# StasDuino_V2.net
KiCad netlist of a schematic drawn in EAGLE
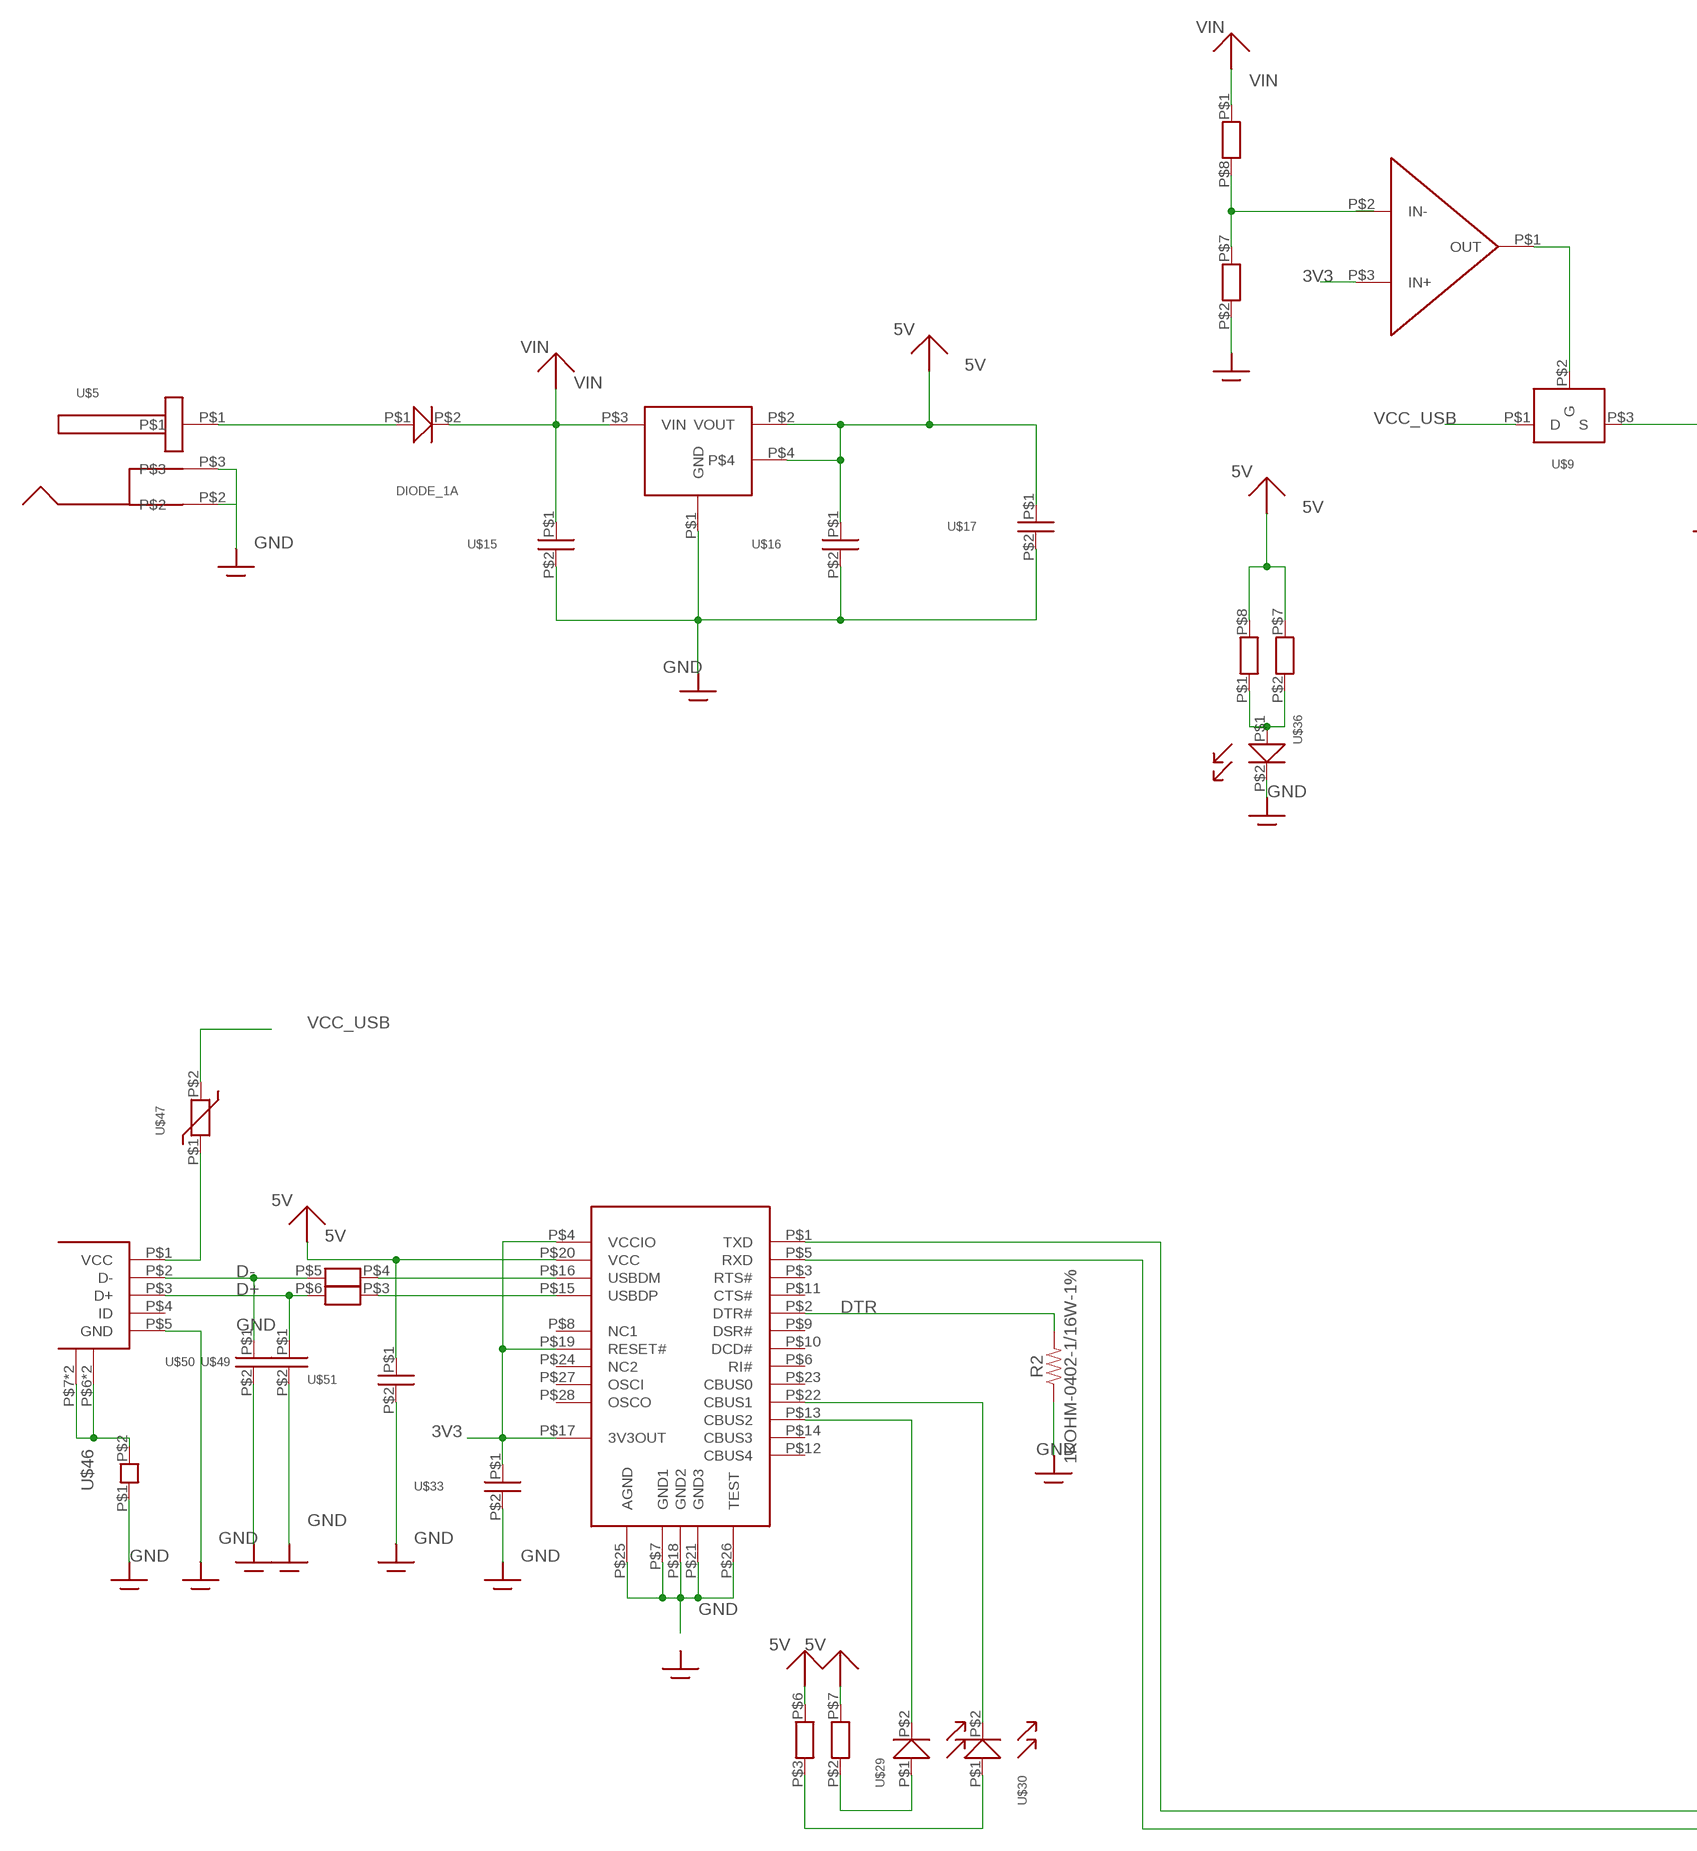
[diagram p0: schematic, sheet 1, part 1 of 2]
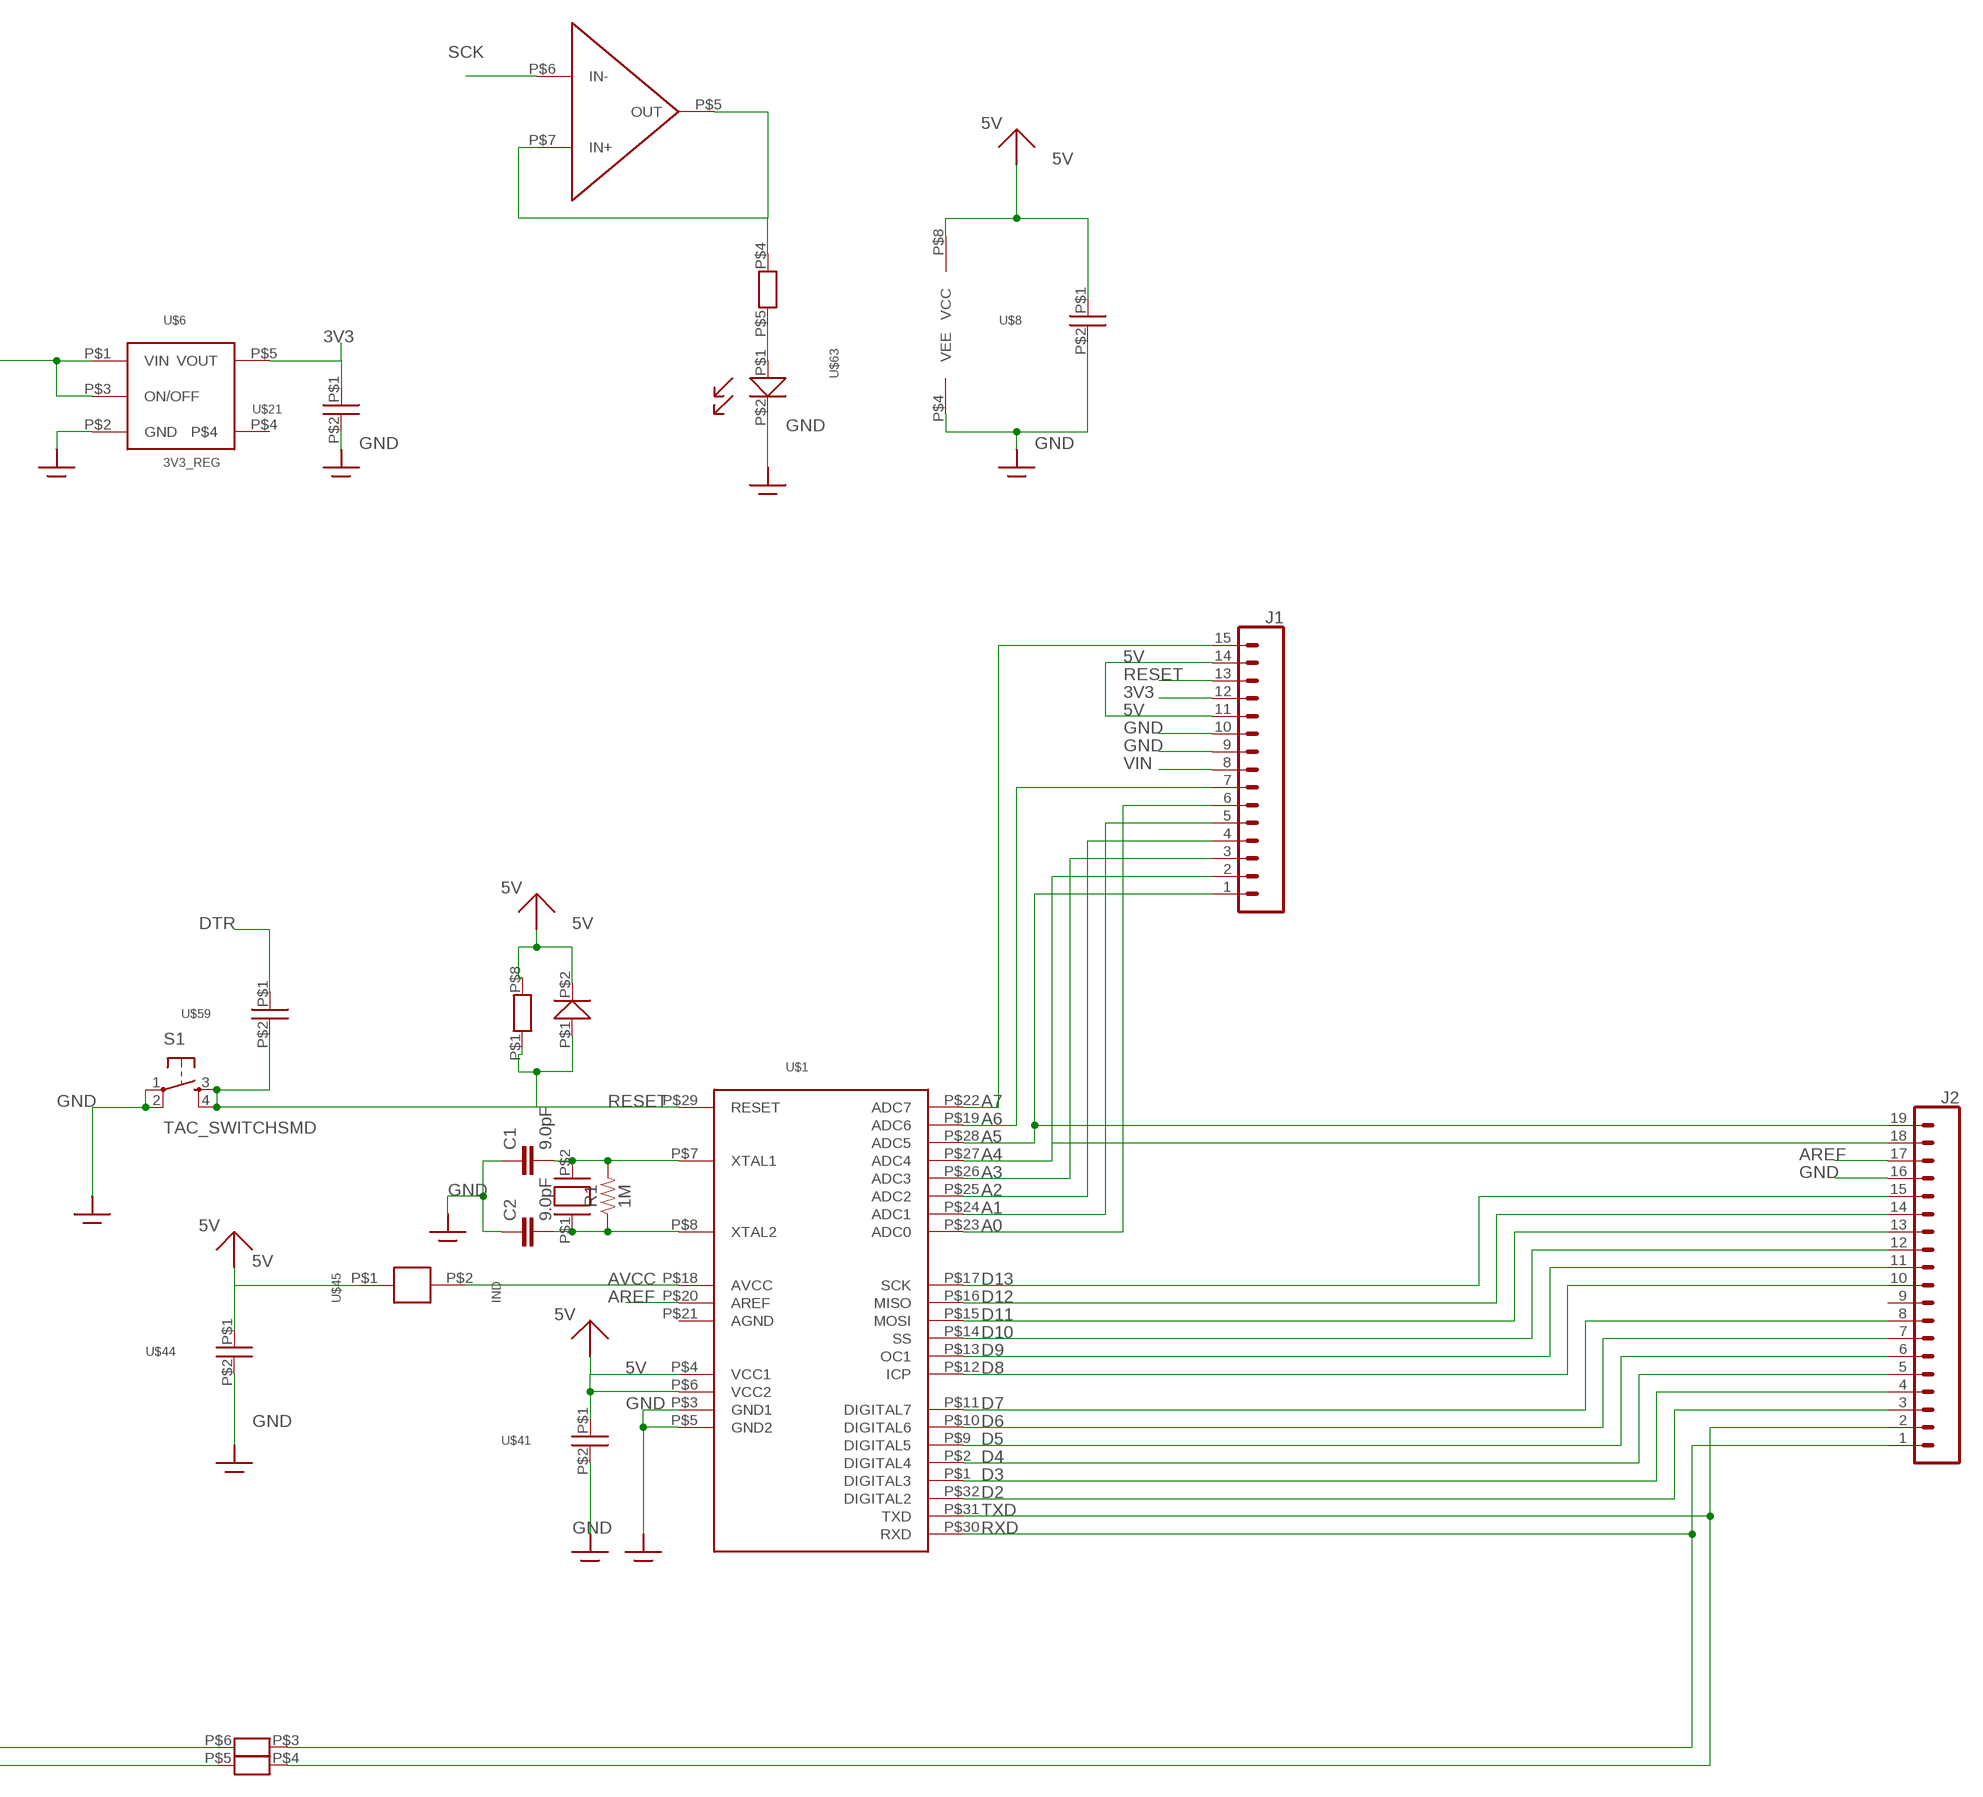
[diagram p1: schematic, sheet 1, part 2 of 2]

(export (version "E")
  (design (tool "Eeschema 10.0.6"))
  (components
    (comp (ref "C1")
      (value "9.0pF")
      (footprint "eagle-import:0603")
      (libsource (lib "eagle-import") (part "9.0PF-0603-50V-10%"))
    )
    (comp (ref "C2")
      (value "9.0pF")
      (footprint "eagle-import:0603")
      (libsource (lib "eagle-import") (part "9.0PF-0603-50V-10%"))
    )
    (comp (ref "J1")
      (value "CONN_15")
      (footprint "eagle-import:1X15")
      (libsource (lib "eagle-import") (part "CONN_15"))
    )
    (comp (ref "J2")
      (value "CONN_19")
      (footprint "eagle-import:1X19")
      (libsource (lib "eagle-import") (part "CONN_19"))
    )
    (comp (ref "R1")
      (value "1M")
      (footprint "eagle-import:0603")
      (libsource (lib "eagle-import") (part "1MOHM-0603-1/4W-5%"))
    )
    (comp (ref "R2")
      (value "1KOHM-0402-1/16W-1%")
      (footprint "eagle-import:0402")
      (libsource (lib "eagle-import") (part "1KOHM-0402-1/16W-1%"))
    )
    (comp (ref "S1")
      (value "TAC_SWITCHSMD")
      (footprint "eagle-import:TACTILE-SWITCH-SMD")
      (libsource (lib "eagle-import") (part "TAC_SWITCHSMD"))
    )
    (comp (ref "U$1")
      (value "ATMEGA328P_TQFP")
      (footprint "eagle-import:ATMEGA328P_TQFP")
      (libsource (lib "eagle-import") (part "ATMEGA328P_TQFP"))
    )
    (comp (ref "U$2")
      (value "FTDI_SERIAL")
      (footprint "eagle-import:FTDI_SERIAL")
      (libsource (lib "eagle-import") (part "FTDI_SERIAL"))
    )
    (comp (ref "U$3")
      (value "USB_MICRO")
      (footprint "eagle-import:USB_MICRO")
      (libsource (lib "eagle-import") (part "USB_MICRO"))
    )
    (comp (ref "U$4")
      (value "5V_REG")
      (footprint "eagle-import:5V_REG")
      (libsource (lib "eagle-import") (part "5V_REG"))
    )
    (comp (ref "U$5")
      (value "DC_POWERJACK")
      (footprint "eagle-import:DC_POWERJACK")
      (libsource (lib "eagle-import") (part "DC_POWERJACK"))
    )
    (comp (ref "U$6")
      (value "3V3_REG")
      (footprint "eagle-import:3V3_REG")
      (libsource (lib "eagle-import") (part "3V3_REG"))
    )
    (comp (ref "U$7")
      (value "OPAMP")
      (footprint "eagle-import:OPAMP")
      (libsource (lib "eagle-import") (part "OPAMP"))
    )
    (comp (ref "U$8")
      (value "CAP_0805")
      (footprint "eagle-import:CAP_0805")
      (libsource (lib "eagle-import") (part "CAP_0805"))
    )
    (comp (ref "U$9")
      (value "PMOS")
      (footprint "eagle-import:PMOS")
      (libsource (lib "eagle-import") (part "PMOS"))
    )
    (comp (ref "U$12")
      (value "DIODE_1A")
      (footprint "eagle-import:DIODE_1A")
      (libsource (lib "eagle-import") (part "DIODE_1A"))
    )
    (comp (ref "U$15")
      (value "CAP_0805")
      (footprint "eagle-import:CAP_0805")
      (libsource (lib "eagle-import") (part "CAP_0805"))
    )
    (comp (ref "U$16")
      (value "CAP_0805")
      (footprint "eagle-import:CAP_0805")
      (libsource (lib "eagle-import") (part "CAP_0805"))
    )
    (comp (ref "U$17")
      (value "CAP_0805")
      (footprint "eagle-import:CAP_0805")
      (libsource (lib "eagle-import") (part "CAP_0805"))
    )
    (comp (ref "U$20")
      (value "RES_ARRAY")
      (footprint "eagle-import:RES_ARRAY")
      (libsource (lib "eagle-import") (part "RES_ARRAY"))
    )
    (comp (ref "U$21")
      (value "CAP_0805")
      (footprint "eagle-import:CAP_0805")
      (libsource (lib "eagle-import") (part "CAP_0805"))
    )
    (comp (ref "U$29")
      (value "LED_0805")
      (footprint "eagle-import:LED_0805")
      (libsource (lib "eagle-import") (part "LED_0805"))
    )
    (comp (ref "U$30")
      (value "LED_0805")
      (footprint "eagle-import:LED_0805")
      (libsource (lib "eagle-import") (part "LED_0805"))
    )
    (comp (ref "U$33")
      (value "CAP_0805")
      (footprint "eagle-import:CAP_0805")
      (libsource (lib "eagle-import") (part "CAP_0805"))
    )
    (comp (ref "U$34")
      (value "RES_ARRAY")
      (footprint "eagle-import:RES_ARRAY")
      (libsource (lib "eagle-import") (part "RES_ARRAY"))
    )
    (comp (ref "U$36")
      (value "LED_0805")
      (footprint "eagle-import:LED_0805")
      (libsource (lib "eagle-import") (part "LED_0805"))
    )
    (comp (ref "U$41")
      (value "CAP_0805")
      (footprint "eagle-import:CAP_0805")
      (libsource (lib "eagle-import") (part "CAP_0805"))
    )
    (comp (ref "U$44")
      (value "CAP_0805")
      (footprint "eagle-import:CAP_0805")
      (libsource (lib "eagle-import") (part "CAP_0805"))
    )
    (comp (ref "U$45")
      (value "IND")
      (footprint "eagle-import:IND")
      (libsource (lib "eagle-import") (part "IND"))
    )
    (comp (ref "U$46")
      (value "FERRITE_BEAD")
      (footprint "eagle-import:FERRITE_BEAD")
      (libsource (lib "eagle-import") (part "FERRITE_BEAD"))
    )
    (comp (ref "U$47")
      (value "RESET_FUSE")
      (footprint "eagle-import:RESET_FUSE")
      (libsource (lib "eagle-import") (part "RESET_FUSE"))
    )
    (comp (ref "U$48")
      (value "RES_ARRAY")
      (footprint "eagle-import:RES_ARRAY")
      (libsource (lib "eagle-import") (part "RES_ARRAY"))
    )
    (comp (ref "U$49")
      (value "CAP_0805")
      (footprint "eagle-import:CAP_0805")
      (libsource (lib "eagle-import") (part "CAP_0805"))
    )
    (comp (ref "U$50")
      (value "CAP_0805")
      (footprint "eagle-import:CAP_0805")
      (libsource (lib "eagle-import") (part "CAP_0805"))
    )
    (comp (ref "U$51")
      (value "CAP_0805")
      (footprint "eagle-import:CAP_0805")
      (libsource (lib "eagle-import") (part "CAP_0805"))
    )
    (comp (ref "U$57")
      (value "CRYSTAL")
      (footprint "eagle-import:CRYSTAL")
      (libsource (lib "eagle-import") (part "CRYSTAL"))
    )
    (comp (ref "U$59")
      (value "CAP_0805")
      (footprint "eagle-import:CAP_0805")
      (libsource (lib "eagle-import") (part "CAP_0805"))
    )
    (comp (ref "U$60")
      (value "DIODE")
      (footprint "eagle-import:DIODE")
      (libsource (lib "eagle-import") (part "DIODE"))
    )
    (comp (ref "U$63")
      (value "LED_0805")
      (footprint "eagle-import:LED_0805")
      (libsource (lib "eagle-import") (part "LED_0805"))
    )
  )
  (nets
    (net (code "1") (name "/3V3") (class "Default")
      (node (ref "J1") (pin "12") (pinfunction "12_12") (pintype "passive"))
      (node (ref "U$2") (pin "P$17") (pinfunction "3V3OUT_P$17") (pintype "bidirectional"))
      (node (ref "U$2") (pin "P$19") (pinfunction "RESET#_P$19") (pintype "bidirectional"))
      (node (ref "U$2") (pin "P$4") (pinfunction "VCCIO_P$4") (pintype "bidirectional"))
      (node (ref "U$21") (pin "P$1") (pinfunction "P$1_P$1") (pintype "bidirectional"))
      (node (ref "U$33") (pin "P$1") (pinfunction "P$1_P$1") (pintype "bidirectional"))
      (node (ref "U$6") (pin "P$5") (pinfunction "VOUT_P$5") (pintype "bidirectional"))
      (node (ref "U$7") (pin "P$3") (pinfunction "IN+_P$3") (pintype "bidirectional"))
    )
    (net (code "2") (name "/5V") (class "Default")
      (node (ref "J1") (pin "11") (pinfunction "11_11") (pintype "passive"))
      (node (ref "J1") (pin "14") (pinfunction "14_14") (pintype "passive"))
      (node (ref "U$1") (pin "P$4") (pinfunction "VCC1_P$4") (pintype "bidirectional"))
      (node (ref "U$1") (pin "P$6") (pinfunction "VCC2_P$6") (pintype "bidirectional"))
      (node (ref "U$16") (pin "P$1") (pinfunction "P$1_P$1") (pintype "bidirectional"))
      (node (ref "U$17") (pin "P$1") (pinfunction "P$1_P$1") (pintype "bidirectional"))
      (node (ref "U$2") (pin "P$20") (pinfunction "VCC_P$20") (pintype "bidirectional"))
      (node (ref "U$34") (pin "P$7") (pinfunction "P$2_P$7") (pintype "bidirectional"))
      (node (ref "U$34") (pin "P$8") (pinfunction "P$2_P$8") (pintype "bidirectional"))
      (node (ref "U$4") (pin "P$2") (pinfunction "VOUT_P$2") (pintype "bidirectional"))
      (node (ref "U$4") (pin "P$4") (pinfunction "P$4_P$4") (pintype "bidirectional"))
      (node (ref "U$41") (pin "P$1") (pinfunction "P$1_P$1") (pintype "bidirectional"))
      (node (ref "U$44") (pin "P$1") (pinfunction "P$1_P$1") (pintype "bidirectional"))
      (node (ref "U$45") (pin "P$1") (pinfunction "P$1_P$1") (pintype "bidirectional"))
      (node (ref "U$48") (pin "P$6") (pinfunction "P$2_P$6") (pintype "bidirectional"))
      (node (ref "U$48") (pin "P$7") (pinfunction "P$2_P$7") (pintype "bidirectional"))
      (node (ref "U$48") (pin "P$8") (pinfunction "P$2_P$8") (pintype "bidirectional"))
      (node (ref "U$51") (pin "P$1") (pinfunction "P$1_P$1") (pintype "bidirectional"))
      (node (ref "U$60") (pin "P$2") (pinfunction "P$2_P$2") (pintype "bidirectional"))
      (node (ref "U$7") (pin "P$8") (pinfunction "VCC_P$8") (pintype "bidirectional"))
      (node (ref "U$8") (pin "P$1") (pinfunction "P$1_P$1") (pintype "bidirectional"))
    )
    (net (code "3") (name "/A0") (class "Default")
      (node (ref "J1") (pin "6") (pinfunction "6_6") (pintype "passive"))
      (node (ref "U$1") (pin "P$23") (pinfunction "ADC0_P$23") (pintype "bidirectional"))
    )
    (net (code "4") (name "/A1") (class "Default")
      (node (ref "J1") (pin "5") (pinfunction "5_5") (pintype "passive"))
      (node (ref "U$1") (pin "P$24") (pinfunction "ADC1_P$24") (pintype "bidirectional"))
    )
    (net (code "5") (name "/A2") (class "Default")
      (node (ref "J1") (pin "4") (pinfunction "4_4") (pintype "passive"))
      (node (ref "U$1") (pin "P$25") (pinfunction "ADC2_P$25") (pintype "bidirectional"))
    )
    (net (code "6") (name "/A3") (class "Default")
      (node (ref "J1") (pin "3") (pinfunction "3_3") (pintype "passive"))
      (node (ref "U$1") (pin "P$26") (pinfunction "ADC3_P$26") (pintype "bidirectional"))
    )
    (net (code "7") (name "/A4") (class "Default")
      (node (ref "J1") (pin "2") (pinfunction "2_2") (pintype "passive"))
      (node (ref "J2") (pin "18") (pinfunction "18_18") (pintype "passive"))
      (node (ref "U$1") (pin "P$27") (pinfunction "ADC4_P$27") (pintype "bidirectional"))
    )
    (net (code "8") (name "/A5") (class "Default")
      (node (ref "J1") (pin "1") (pinfunction "1_1") (pintype "passive"))
      (node (ref "J2") (pin "19") (pinfunction "19_19") (pintype "passive"))
      (node (ref "U$1") (pin "P$28") (pinfunction "ADC5_P$28") (pintype "bidirectional"))
    )
    (net (code "9") (name "/A6") (class "Default")
      (node (ref "J1") (pin "7") (pinfunction "7_7") (pintype "passive"))
      (node (ref "U$1") (pin "P$19") (pinfunction "ADC6_P$19") (pintype "bidirectional"))
    )
    (net (code "10") (name "/A7") (class "Default")
      (node (ref "J1") (pin "15") (pinfunction "15_15") (pintype "passive"))
      (node (ref "U$1") (pin "P$22") (pinfunction "ADC7_P$22") (pintype "bidirectional"))
    )
    (net (code "11") (name "/AREF") (class "Default")
      (node (ref "J2") (pin "17") (pinfunction "17_17") (pintype "passive"))
      (node (ref "U$1") (pin "P$20") (pinfunction "AREF_P$20") (pintype "bidirectional"))
    )
    (net (code "12") (name "/AVCC") (class "Default")
      (node (ref "U$1") (pin "P$18") (pinfunction "AVCC_P$18") (pintype "bidirectional"))
      (node (ref "U$45") (pin "P$2") (pinfunction "P$2_P$2") (pintype "bidirectional"))
    )
    (net (code "13") (name "/D+") (class "Default")
      (node (ref "U$20") (pin "P$6") (pinfunction "P$2_P$6") (pintype "bidirectional"))
      (node (ref "U$3") (pin "P$3") (pinfunction "D+_P$3") (pintype "bidirectional"))
      (node (ref "U$49") (pin "P$1") (pinfunction "P$1_P$1") (pintype "bidirectional"))
    )
    (net (code "14") (name "/D-") (class "Default")
      (node (ref "U$20") (pin "P$5") (pinfunction "P$2_P$5") (pintype "bidirectional"))
      (node (ref "U$3") (pin "P$2") (pinfunction "D-_P$2") (pintype "bidirectional"))
      (node (ref "U$50") (pin "P$1") (pinfunction "P$1_P$1") (pintype "bidirectional"))
    )
    (net (code "15") (name "/D2") (class "Default")
      (node (ref "J2") (pin "3") (pinfunction "3_3") (pintype "passive"))
      (node (ref "U$1") (pin "P$32") (pinfunction "DIGITAL2_P$32") (pintype "bidirectional"))
    )
    (net (code "16") (name "/D3") (class "Default")
      (node (ref "J2") (pin "4") (pinfunction "4_4") (pintype "passive"))
      (node (ref "U$1") (pin "P$1") (pinfunction "DIGITAL3_P$1") (pintype "bidirectional"))
    )
    (net (code "17") (name "/D4") (class "Default")
      (node (ref "J2") (pin "5") (pinfunction "5_5") (pintype "passive"))
      (node (ref "U$1") (pin "P$2") (pinfunction "DIGITAL4_P$2") (pintype "bidirectional"))
    )
    (net (code "18") (name "/D5") (class "Default")
      (node (ref "J2") (pin "6") (pinfunction "6_6") (pintype "passive"))
      (node (ref "U$1") (pin "P$9") (pinfunction "DIGITAL5_P$9") (pintype "bidirectional"))
    )
    (net (code "19") (name "/D6") (class "Default")
      (node (ref "J2") (pin "7") (pinfunction "7_7") (pintype "passive"))
      (node (ref "U$1") (pin "P$10") (pinfunction "DIGITAL6_P$10") (pintype "bidirectional"))
    )
    (net (code "20") (name "/D7") (class "Default")
      (node (ref "J2") (pin "8") (pinfunction "8_8") (pintype "passive"))
      (node (ref "U$1") (pin "P$11") (pinfunction "DIGITAL7_P$11") (pintype "bidirectional"))
    )
    (net (code "21") (name "/D8") (class "Default")
      (node (ref "J2") (pin "10") (pinfunction "10_10") (pintype "passive"))
      (node (ref "U$1") (pin "P$12") (pinfunction "ICP_P$12") (pintype "bidirectional"))
    )
    (net (code "22") (name "/D9") (class "Default")
      (node (ref "J2") (pin "11") (pinfunction "11_11") (pintype "passive"))
      (node (ref "U$1") (pin "P$13") (pinfunction "OC1_P$13") (pintype "bidirectional"))
    )
    (net (code "23") (name "/D10") (class "Default")
      (node (ref "J2") (pin "12") (pinfunction "12_12") (pintype "passive"))
      (node (ref "U$1") (pin "P$14") (pinfunction "SS_P$14") (pintype "bidirectional"))
    )
    (net (code "24") (name "/D11") (class "Default")
      (node (ref "J2") (pin "13") (pinfunction "13_13") (pintype "passive"))
      (node (ref "U$1") (pin "P$15") (pinfunction "MOSI_P$15") (pintype "bidirectional"))
    )
    (net (code "25") (name "/D12") (class "Default")
      (node (ref "J2") (pin "14") (pinfunction "14_14") (pintype "passive"))
      (node (ref "U$1") (pin "P$16") (pinfunction "MISO_P$16") (pintype "bidirectional"))
    )
    (net (code "26") (name "/D13") (class "Default")
      (node (ref "J2") (pin "15") (pinfunction "15_15") (pintype "passive"))
      (node (ref "U$1") (pin "P$17") (pinfunction "SCK_P$17") (pintype "bidirectional"))
    )
    (net (code "27") (name "/DTR") (class "Default")
      (node (ref "R2") (pin "2") (pinfunction "2_2") (pintype "passive"))
      (node (ref "U$2") (pin "P$2") (pinfunction "DTR#_P$2") (pintype "bidirectional"))
      (node (ref "U$59") (pin "P$1") (pinfunction "P$1_P$1") (pintype "bidirectional"))
    )
    (net (code "28") (name "/GND") (class "Default")
      (node (ref "C1") (pin "1") (pinfunction "1_1") (pintype "passive"))
      (node (ref "C2") (pin "1") (pinfunction "1_1") (pintype "passive"))
      (node (ref "J1") (pin "10") (pinfunction "10_10") (pintype "passive"))
      (node (ref "J1") (pin "9") (pinfunction "9_9") (pintype "passive"))
      (node (ref "J2") (pin "16") (pinfunction "16_16") (pintype "passive"))
      (node (ref "R2") (pin "1") (pinfunction "1_1") (pintype "passive"))
      (node (ref "S1") (pin "1") (pinfunction "1_1") (pintype "passive"))
      (node (ref "S1") (pin "2") (pinfunction "2_2") (pintype "passive"))
      (node (ref "U$1") (pin "P$3") (pinfunction "GND1_P$3") (pintype "bidirectional"))
      (node (ref "U$1") (pin "P$5") (pinfunction "GND2_P$5") (pintype "bidirectional"))
      (node (ref "U$15") (pin "P$2") (pinfunction "P$2_P$2") (pintype "bidirectional"))
      (node (ref "U$16") (pin "P$2") (pinfunction "P$2_P$2") (pintype "bidirectional"))
      (node (ref "U$17") (pin "P$2") (pinfunction "P$2_P$2") (pintype "bidirectional"))
      (node (ref "U$2") (pin "P$18") (pinfunction "GND2_P$18") (pintype "bidirectional"))
      (node (ref "U$2") (pin "P$21") (pinfunction "GND3_P$21") (pintype "bidirectional"))
      (node (ref "U$2") (pin "P$25") (pinfunction "AGND_P$25") (pintype "bidirectional"))
      (node (ref "U$2") (pin "P$26") (pinfunction "TEST_P$26") (pintype "bidirectional"))
      (node (ref "U$2") (pin "P$7") (pinfunction "GND1_P$7") (pintype "bidirectional"))
      (node (ref "U$20") (pin "P$2") (pinfunction "P$1_P$2") (pintype "bidirectional"))
      (node (ref "U$21") (pin "P$2") (pinfunction "P$2_P$2") (pintype "bidirectional"))
      (node (ref "U$3") (pin "P$5") (pinfunction "GND_P$5") (pintype "bidirectional"))
      (node (ref "U$33") (pin "P$2") (pinfunction "P$2_P$2") (pintype "bidirectional"))
      (node (ref "U$36") (pin "P$2") (pinfunction "P$2_P$2") (pintype "bidirectional"))
      (node (ref "U$4") (pin "P$1") (pinfunction "GND_P$1") (pintype "bidirectional"))
      (node (ref "U$41") (pin "P$2") (pinfunction "P$2_P$2") (pintype "bidirectional"))
      (node (ref "U$44") (pin "P$2") (pinfunction "P$2_P$2") (pintype "bidirectional"))
      (node (ref "U$46") (pin "P$1") (pinfunction "P$1_P$1") (pintype "bidirectional"))
      (node (ref "U$49") (pin "P$2") (pinfunction "P$2_P$2") (pintype "bidirectional"))
      (node (ref "U$5") (pin "P$2") (pinfunction "P$2_P$2") (pintype "bidirectional"))
      (node (ref "U$5") (pin "P$3") (pinfunction "P$3_P$3") (pintype "bidirectional"))
      (node (ref "U$50") (pin "P$2") (pinfunction "P$2_P$2") (pintype "bidirectional"))
      (node (ref "U$51") (pin "P$2") (pinfunction "P$2_P$2") (pintype "bidirectional"))
      (node (ref "U$6") (pin "P$2") (pinfunction "GND_P$2") (pintype "bidirectional"))
      (node (ref "U$63") (pin "P$2") (pinfunction "P$2_P$2") (pintype "bidirectional"))
      (node (ref "U$7") (pin "P$4") (pinfunction "VEE_P$4") (pintype "bidirectional"))
      (node (ref "U$8") (pin "P$2") (pinfunction "P$2_P$2") (pintype "bidirectional"))
    )
    (net (code "29") (name "/RESET") (class "Default")
      (node (ref "J1") (pin "13") (pinfunction "13_13") (pintype "passive"))
      (node (ref "S1") (pin "3") (pinfunction "3_3") (pintype "passive"))
      (node (ref "S1") (pin "4") (pinfunction "4_4") (pintype "passive"))
      (node (ref "U$1") (pin "P$29") (pinfunction "RESET_P$29") (pintype "bidirectional"))
      (node (ref "U$48") (pin "P$1") (pinfunction "P$1_P$1") (pintype "bidirectional"))
      (node (ref "U$59") (pin "P$2") (pinfunction "P$2_P$2") (pintype "bidirectional"))
      (node (ref "U$60") (pin "P$1") (pinfunction "P$1_P$1") (pintype "bidirectional"))
    )
    (net (code "30") (name "/RXD") (class "Default")
      (node (ref "J2") (pin "1") (pinfunction "1_1") (pintype "passive"))
      (node (ref "U$1") (pin "P$30") (pinfunction "RXD_P$30") (pintype "bidirectional"))
      (node (ref "U$34") (pin "P$3") (pinfunction "P$1_P$3") (pintype "bidirectional"))
    )
    (net (code "31") (name "/SCK") (class "Default")
      (node (ref "U$7") (pin "P$6") (pinfunction "IN-_P$6") (pintype "bidirectional"))
    )
    (net (code "32") (name "/TXD") (class "Default")
      (node (ref "J2") (pin "2") (pinfunction "2_2") (pintype "passive"))
      (node (ref "U$1") (pin "P$31") (pinfunction "TXD_P$31") (pintype "bidirectional"))
      (node (ref "U$34") (pin "P$4") (pinfunction "P$1_P$4") (pintype "bidirectional"))
    )
    (net (code "33") (name "/VCC_USB") (class "Default")
      (node (ref "U$47") (pin "P$2") (pinfunction "P$2_P$2") (pintype "bidirectional"))
      (node (ref "U$9") (pin "P$1") (pinfunction "D_P$1") (pintype "bidirectional"))
    )
    (net (code "34") (name "/VIN") (class "Default")
      (node (ref "J1") (pin "8") (pinfunction "8_8") (pintype "passive"))
      (node (ref "U$12") (pin "P$2") (pinfunction "P$2_P$2") (pintype "bidirectional"))
      (node (ref "U$15") (pin "P$1") (pinfunction "P$1_P$1") (pintype "bidirectional"))
      (node (ref "U$20") (pin "P$1") (pinfunction "P$1_P$1") (pintype "bidirectional"))
      (node (ref "U$4") (pin "P$3") (pinfunction "VIN_P$3") (pintype "bidirectional"))
    )
    (net (code "35") (name "Net-(U$1-XTAL1)") (class "Default")
      (node (ref "C1") (pin "2") (pinfunction "2_2") (pintype "passive"))
      (node (ref "R1") (pin "2") (pinfunction "2_2") (pintype "passive"))
      (node (ref "U$1") (pin "P$7") (pinfunction "XTAL1_P$7") (pintype "bidirectional"))
      (node (ref "U$57") (pin "P$2") (pinfunction "P$2_P$2") (pintype "bidirectional"))
    )
    (net (code "36") (name "Net-(U$1-XTAL2)") (class "Default")
      (node (ref "C2") (pin "2") (pinfunction "2_2") (pintype "passive"))
      (node (ref "R1") (pin "1") (pinfunction "1_1") (pintype "passive"))
      (node (ref "U$1") (pin "P$8") (pinfunction "XTAL2_P$8") (pintype "bidirectional"))
      (node (ref "U$57") (pin "P$1") (pinfunction "P$1_P$1") (pintype "bidirectional"))
    )
    (net (code "37") (name "Net-(U$2-CBUS1)") (class "Default")
      (node (ref "U$2") (pin "P$22") (pinfunction "CBUS1_P$22") (pintype "bidirectional"))
      (node (ref "U$30") (pin "P$2") (pinfunction "P$2_P$2") (pintype "bidirectional"))
    )
    (net (code "38") (name "Net-(U$2-CBUS2)") (class "Default")
      (node (ref "U$2") (pin "P$13") (pinfunction "CBUS2_P$13") (pintype "bidirectional"))
      (node (ref "U$29") (pin "P$2") (pinfunction "P$2_P$2") (pintype "bidirectional"))
    )
    (net (code "39") (name "Net-(U$2-RXD)") (class "Default")
      (node (ref "U$2") (pin "P$5") (pinfunction "RXD_P$5") (pintype "bidirectional"))
      (node (ref "U$34") (pin "P$5") (pinfunction "P$2_P$5") (pintype "bidirectional"))
    )
    (net (code "40") (name "Net-(U$2-TXD)") (class "Default")
      (node (ref "U$2") (pin "P$1") (pinfunction "TXD_P$1") (pintype "bidirectional"))
      (node (ref "U$34") (pin "P$6") (pinfunction "P$2_P$6") (pintype "bidirectional"))
    )
    (net (code "41") (name "Net-(U$2-USBDM)") (class "Default")
      (node (ref "U$2") (pin "P$16") (pinfunction "USBDM_P$16") (pintype "bidirectional"))
      (node (ref "U$20") (pin "P$4") (pinfunction "P$1_P$4") (pintype "bidirectional"))
    )
    (net (code "42") (name "Net-(U$2-USBDP)") (class "Default")
      (node (ref "U$2") (pin "P$15") (pinfunction "USBDP_P$15") (pintype "bidirectional"))
      (node (ref "U$20") (pin "P$3") (pinfunction "P$1_P$3") (pintype "bidirectional"))
    )
    (net (code "43") (name "Net-(U$3-SHIELD1-PadP$6)") (class "Default")
      (node (ref "U$3") (pin "P$6") (pinfunction "SHIELD1_P$6") (pintype "bidirectional"))
      (node (ref "U$3") (pin "P$7") (pinfunction "SHIELD2_P$7") (pintype "bidirectional"))
      (node (ref "U$3") (pin "P$8") (pinfunction "SHIELD1_P$8") (pintype "bidirectional"))
      (node (ref "U$3") (pin "P$9") (pinfunction "SHIELD2_P$9") (pintype "bidirectional"))
      (node (ref "U$46") (pin "P$2") (pinfunction "P$2_P$2") (pintype "bidirectional"))
    )
    (net (code "44") (name "Net-(U$3-VCC)") (class "Default")
      (node (ref "U$3") (pin "P$1") (pinfunction "VCC_P$1") (pintype "bidirectional"))
      (node (ref "U$47") (pin "P$1") (pinfunction "P$1_P$1") (pintype "bidirectional"))
    )
    (net (code "45") (name "Net-(U$6-ON{slash}OFF)") (class "Default")
      (node (ref "U$6") (pin "P$1") (pinfunction "VIN_P$1") (pintype "bidirectional"))
      (node (ref "U$6") (pin "P$3") (pinfunction "ON/OFF_P$3") (pintype "bidirectional"))
      (node (ref "U$9") (pin "P$3") (pinfunction "S_P$3") (pintype "bidirectional"))
    )
    (net (code "46") (name "Net-(U$7A-OUT)") (class "Default")
      (node (ref "U$7") (pin "P$1") (pinfunction "OUT_P$1") (pintype "bidirectional"))
      (node (ref "U$9") (pin "P$2") (pinfunction "G_P$2") (pintype "bidirectional"))
    )
    (net (code "47") (name "Net-(U$12-PadP$1)") (class "Default")
      (node (ref "U$12") (pin "P$1") (pinfunction "P$1_P$1") (pintype "bidirectional"))
      (node (ref "U$5") (pin "P$1") (pinfunction "P$1_P$1") (pintype "bidirectional"))
    )
    (net (code "48") (name "Net-(U$20A-P$2)") (class "Default")
      (node (ref "U$20") (pin "P$7") (pinfunction "P$2_P$7") (pintype "bidirectional"))
      (node (ref "U$20") (pin "P$8") (pinfunction "P$2_P$8") (pintype "bidirectional"))
      (node (ref "U$7") (pin "P$2") (pinfunction "IN-_P$2") (pintype "bidirectional"))
    )
    (net (code "49") (name "Net-(U$34B-P$1)") (class "Default")
      (node (ref "U$34") (pin "P$1") (pinfunction "P$1_P$1") (pintype "bidirectional"))
      (node (ref "U$34") (pin "P$2") (pinfunction "P$1_P$2") (pintype "bidirectional"))
      (node (ref "U$36") (pin "P$1") (pinfunction "P$1_P$1") (pintype "bidirectional"))
    )
    (net (code "50") (name "Net-(U$48B-P$1)") (class "Default")
      (node (ref "U$29") (pin "P$1") (pinfunction "P$1_P$1") (pintype "bidirectional"))
      (node (ref "U$48") (pin "P$2") (pinfunction "P$1_P$2") (pintype "bidirectional"))
    )
    (net (code "51") (name "Net-(U$48C-P$1)") (class "Default")
      (node (ref "U$30") (pin "P$1") (pinfunction "P$1_P$1") (pintype "bidirectional"))
      (node (ref "U$48") (pin "P$3") (pinfunction "P$1_P$3") (pintype "bidirectional"))
    )
    (net (code "52") (name "Net-(U$48D-P$1)") (class "Default")
      (node (ref "U$48") (pin "P$4") (pinfunction "P$1_P$4") (pintype "bidirectional"))
      (node (ref "U$7") (pin "P$5") (pinfunction "OUT_P$5") (pintype "bidirectional"))
      (node (ref "U$7") (pin "P$7") (pinfunction "IN+_P$7") (pintype "bidirectional"))
    )
    (net (code "53") (name "Net-(U$48D-P$2)") (class "Default")
      (node (ref "U$48") (pin "P$5") (pinfunction "P$2_P$5") (pintype "bidirectional"))
      (node (ref "U$63") (pin "P$1") (pinfunction "P$1_P$1") (pintype "bidirectional"))
    )
    (net (code "54") (name "unconnected-(J2-Pad9)") (class "Default")
      (node (ref "J2") (pin "9") (pinfunction "9_9") (pintype "passive"))
    )
    (net (code "55") (name "unconnected-(U$1-AGND-PadP$21)") (class "Default")
      (node (ref "U$1") (pin "P$21") (pinfunction "AGND_P$21") (pintype "bidirectional"))
    )
    (net (code "56") (name "unconnected-(U$2-CBUS0-PadP$23)") (class "Default")
      (node (ref "U$2") (pin "P$23") (pinfunction "CBUS0_P$23") (pintype "bidirectional"))
    )
    (net (code "57") (name "unconnected-(U$2-CBUS3-PadP$14)") (class "Default")
      (node (ref "U$2") (pin "P$14") (pinfunction "CBUS3_P$14") (pintype "bidirectional"))
    )
    (net (code "58") (name "unconnected-(U$2-CBUS4-PadP$12)") (class "Default")
      (node (ref "U$2") (pin "P$12") (pinfunction "CBUS4_P$12") (pintype "bidirectional"))
    )
    (net (code "59") (name "unconnected-(U$2-CTS#-PadP$11)") (class "Default")
      (node (ref "U$2") (pin "P$11") (pinfunction "CTS#_P$11") (pintype "bidirectional"))
    )
    (net (code "60") (name "unconnected-(U$2-DCD#-PadP$10)") (class "Default")
      (node (ref "U$2") (pin "P$10") (pinfunction "DCD#_P$10") (pintype "bidirectional"))
    )
    (net (code "61") (name "unconnected-(U$2-DSR#-PadP$9)") (class "Default")
      (node (ref "U$2") (pin "P$9") (pinfunction "DSR#_P$9") (pintype "bidirectional"))
    )
    (net (code "62") (name "unconnected-(U$2-NC1-PadP$8)") (class "Default")
      (node (ref "U$2") (pin "P$8") (pinfunction "NC1_P$8") (pintype "no_connect"))
    )
    (net (code "63") (name "unconnected-(U$2-NC2-PadP$24)") (class "Default")
      (node (ref "U$2") (pin "P$24") (pinfunction "NC2_P$24") (pintype "no_connect"))
    )
    (net (code "64") (name "unconnected-(U$2-OSCI-PadP$27)") (class "Default")
      (node (ref "U$2") (pin "P$27") (pinfunction "OSCI_P$27") (pintype "bidirectional"))
    )
    (net (code "65") (name "unconnected-(U$2-OSCO-PadP$28)") (class "Default")
      (node (ref "U$2") (pin "P$28") (pinfunction "OSCO_P$28") (pintype "bidirectional"))
    )
    (net (code "66") (name "unconnected-(U$2-RI#-PadP$6)") (class "Default")
      (node (ref "U$2") (pin "P$6") (pinfunction "RI#_P$6") (pintype "bidirectional"))
    )
    (net (code "67") (name "unconnected-(U$2-RTS#-PadP$3)") (class "Default")
      (node (ref "U$2") (pin "P$3") (pinfunction "RTS#_P$3") (pintype "bidirectional"))
    )
    (net (code "68") (name "unconnected-(U$3-ID-PadP$4)") (class "Default")
      (node (ref "U$3") (pin "P$4") (pinfunction "ID_P$4") (pintype "no_connect"))
    )
    (net (code "69") (name "unconnected-(U$6-PadP$4)") (class "Default")
      (node (ref "U$6") (pin "P$4") (pinfunction "P$4_P$4") (pintype "no_connect"))
    )
  )
)
